# l298driver.net
KiCad netlist of a schematic drawn in EAGLE
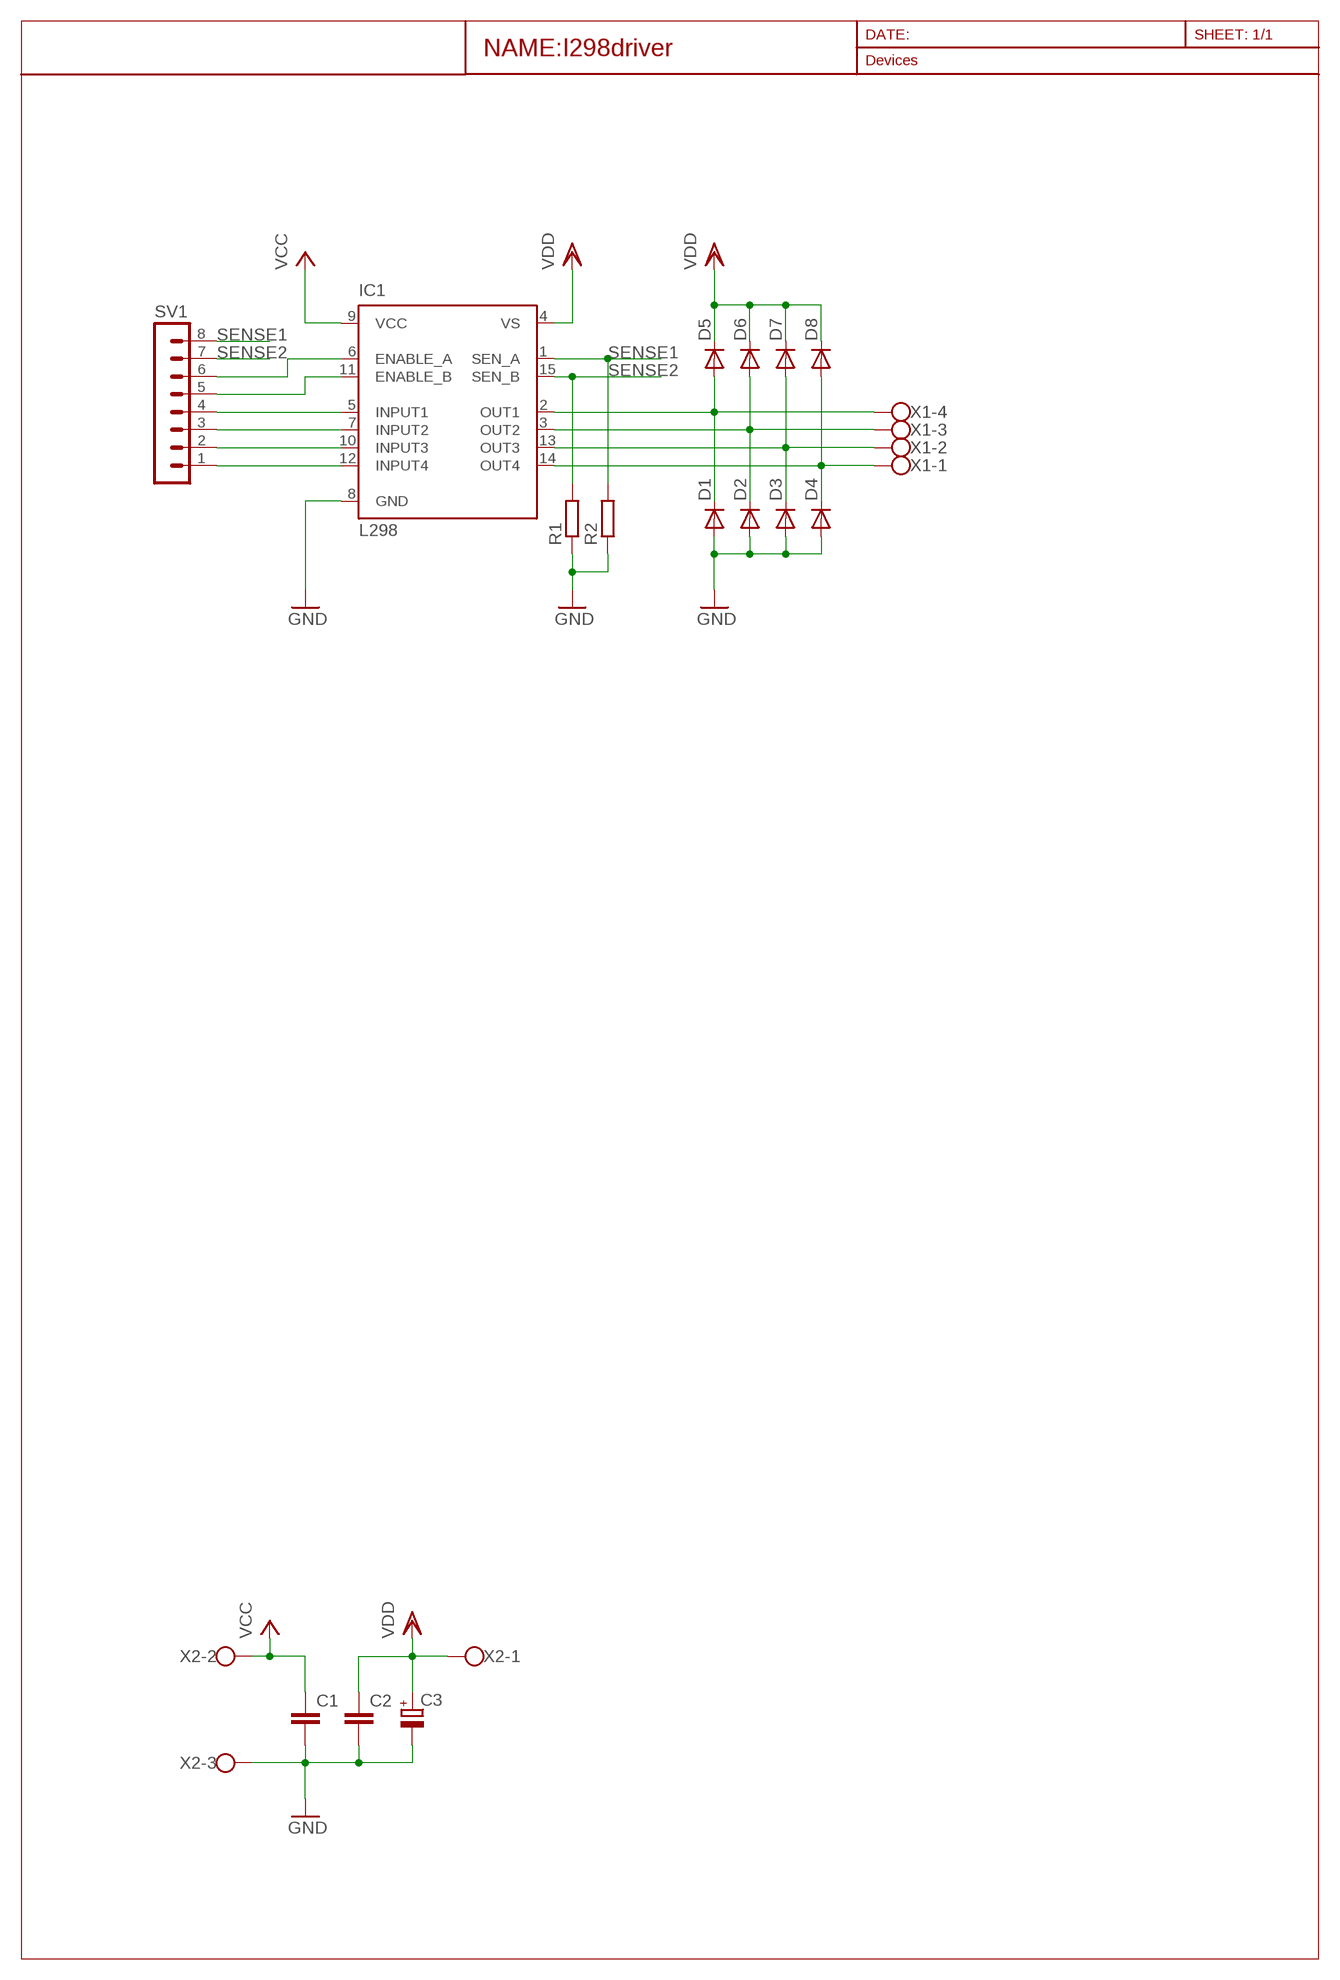
[diagram p0: schematic, sheet 1]

(export (version "E")
  (design (tool "Eeschema 10.0.6"))
  (components
    (comp (ref "C1")
      (value "C-EU050-024X044")
      (footprint "eagle-import:C050-024X044")
      (libsource (lib "eagle-import") (part "C-EU050-024X044"))
    )
    (comp (ref "C2")
      (value "C-EU050-024X044")
      (footprint "eagle-import:C050-024X044")
      (libsource (lib "eagle-import") (part "C-EU050-024X044"))
    )
    (comp (ref "C3")
      (value "CPOL-EUE3.5-10")
      (footprint "eagle-import:E3,5-10")
      (libsource (lib "eagle-import") (part "CPOL-EUE3.5-10"))
    )
    (comp (ref "D1")
      (value "BA157")
      (footprint "eagle-import:P1-10")
      (libsource (lib "eagle-import") (part "BA157"))
    )
    (comp (ref "D2")
      (value "BA157")
      (footprint "eagle-import:P1-10")
      (libsource (lib "eagle-import") (part "BA157"))
    )
    (comp (ref "D3")
      (value "BA157")
      (footprint "eagle-import:P1-10")
      (libsource (lib "eagle-import") (part "BA157"))
    )
    (comp (ref "D4")
      (value "BA157")
      (footprint "eagle-import:P1-10")
      (libsource (lib "eagle-import") (part "BA157"))
    )
    (comp (ref "D5")
      (value "BA157")
      (footprint "eagle-import:P1-10")
      (libsource (lib "eagle-import") (part "BA157"))
    )
    (comp (ref "D6")
      (value "BA157")
      (footprint "eagle-import:P1-10")
      (libsource (lib "eagle-import") (part "BA157"))
    )
    (comp (ref "D7")
      (value "BA157")
      (footprint "eagle-import:P1-10")
      (libsource (lib "eagle-import") (part "BA157"))
    )
    (comp (ref "D8")
      (value "BA157")
      (footprint "eagle-import:P1-10")
      (libsource (lib "eagle-import") (part "BA157"))
    )
    (comp (ref "IC1")
      (value "L298")
      (footprint "eagle-import:MULTIWATT-15")
      (fields (field (name "MPN") "L298N"))
      (libsource (lib "eagle-import") (part "L298"))
    )
    (comp (ref "R1")
      (value "R-EU_RDH/15")
      (footprint "eagle-import:RDH_15")
      (libsource (lib "eagle-import") (part "R-EU_RDH/15"))
    )
    (comp (ref "R2")
      (value "R-EU_RDH/15")
      (footprint "eagle-import:RDH_15")
      (libsource (lib "eagle-import") (part "R-EU_RDH/15"))
    )
    (comp (ref "SV1")
      (value "MA08-1")
      (footprint "eagle-import:MA08-1")
      (libsource (lib "eagle-import") (part "MA08-1"))
    )
    (comp (ref "X1")
      (value "W237-4")
      (footprint "eagle-import:W237-4")
      (libsource (lib "eagle-import") (part "W237-4"))
    )
    (comp (ref "X2")
      (value "W237-103")
      (footprint "eagle-import:W237-103")
      (fields (field (name "MPN") "237-103"))
      (libsource (lib "eagle-import") (part "W237-103"))
    )
  )
  (nets
    (net (code "1") (name "/SENSE1") (class "Default")
      (node (ref "IC1") (pin "1") (pinfunction "SEN_A_1") (pintype "input"))
      (node (ref "R2") (pin "2") (pinfunction "2_2") (pintype "passive"))
      (node (ref "SV1") (pin "8") (pinfunction "8_8") (pintype "passive"))
    )
    (net (code "2") (name "/SENSE2") (class "Default")
      (node (ref "IC1") (pin "15") (pinfunction "SEN_B_15") (pintype "input"))
      (node (ref "R1") (pin "2") (pinfunction "2_2") (pintype "passive"))
      (node (ref "SV1") (pin "7") (pinfunction "7_7") (pintype "passive"))
    )
    (net (code "3") (name "GND") (class "Default")
      (node (ref "C1") (pin "2") (pinfunction "2_2") (pintype "passive"))
      (node (ref "C2") (pin "2") (pinfunction "2_2") (pintype "passive"))
      (node (ref "C3") (pin "-") (pinfunction "-_-") (pintype "passive"))
      (node (ref "D1") (pin "A") (pinfunction "A_A") (pintype "passive"))
      (node (ref "D2") (pin "A") (pinfunction "A_A") (pintype "passive"))
      (node (ref "D3") (pin "A") (pinfunction "A_A") (pintype "passive"))
      (node (ref "D4") (pin "A") (pinfunction "A_A") (pintype "passive"))
      (node (ref "IC1") (pin "8") (pinfunction "GND_8") (pintype "power_in"))
      (node (ref "R1") (pin "1") (pinfunction "1_1") (pintype "passive"))
      (node (ref "R2") (pin "1") (pinfunction "1_1") (pintype "passive"))
      (node (ref "X2") (pin "3") (pinfunction "KL_3") (pintype "passive"))
    )
    (net (code "4") (name "Net-(IC1-ENABLE_A)") (class "Default")
      (node (ref "IC1") (pin "6") (pinfunction "ENABLE_A_6") (pintype "input"))
      (node (ref "SV1") (pin "6") (pinfunction "6_6") (pintype "passive"))
    )
    (net (code "5") (name "Net-(IC1-ENABLE_B)") (class "Default")
      (node (ref "IC1") (pin "11") (pinfunction "ENABLE_B_11") (pintype "input"))
      (node (ref "SV1") (pin "5") (pinfunction "5_5") (pintype "passive"))
    )
    (net (code "6") (name "Net-(IC1-INPUT1)") (class "Default")
      (node (ref "IC1") (pin "5") (pinfunction "INPUT1_5") (pintype "input"))
      (node (ref "SV1") (pin "4") (pinfunction "4_4") (pintype "passive"))
    )
    (net (code "7") (name "Net-(IC1-INPUT2)") (class "Default")
      (node (ref "IC1") (pin "7") (pinfunction "INPUT2_7") (pintype "input"))
      (node (ref "SV1") (pin "3") (pinfunction "3_3") (pintype "passive"))
    )
    (net (code "8") (name "Net-(IC1-INPUT3)") (class "Default")
      (node (ref "IC1") (pin "10") (pinfunction "INPUT3_10") (pintype "input"))
      (node (ref "SV1") (pin "2") (pinfunction "2_2") (pintype "passive"))
    )
    (net (code "9") (name "Net-(IC1-INPUT4)") (class "Default")
      (node (ref "IC1") (pin "12") (pinfunction "INPUT4_12") (pintype "input"))
      (node (ref "SV1") (pin "1") (pinfunction "1_1") (pintype "passive"))
    )
    (net (code "10") (name "Net-(IC1-OUT1)") (class "Default")
      (node (ref "D1") (pin "C") (pinfunction "C_C") (pintype "passive"))
      (node (ref "D5") (pin "A") (pinfunction "A_A") (pintype "passive"))
      (node (ref "IC1") (pin "2") (pinfunction "OUT1_2") (pintype "output"))
      (node (ref "X1") (pin "4") (pinfunction "KL_4") (pintype "passive"))
    )
    (net (code "11") (name "Net-(IC1-OUT2)") (class "Default")
      (node (ref "D2") (pin "C") (pinfunction "C_C") (pintype "passive"))
      (node (ref "D6") (pin "A") (pinfunction "A_A") (pintype "passive"))
      (node (ref "IC1") (pin "3") (pinfunction "OUT2_3") (pintype "output"))
      (node (ref "X1") (pin "3") (pinfunction "KL_3") (pintype "passive"))
    )
    (net (code "12") (name "Net-(IC1-OUT3)") (class "Default")
      (node (ref "D3") (pin "C") (pinfunction "C_C") (pintype "passive"))
      (node (ref "D7") (pin "A") (pinfunction "A_A") (pintype "passive"))
      (node (ref "IC1") (pin "13") (pinfunction "OUT3_13") (pintype "output"))
      (node (ref "X1") (pin "2") (pinfunction "KL_2") (pintype "passive"))
    )
    (net (code "13") (name "Net-(IC1-OUT4)") (class "Default")
      (node (ref "D4") (pin "C") (pinfunction "C_C") (pintype "passive"))
      (node (ref "D8") (pin "A") (pinfunction "A_A") (pintype "passive"))
      (node (ref "IC1") (pin "14") (pinfunction "OUT4_14") (pintype "output"))
      (node (ref "X1") (pin "1") (pinfunction "KL_1") (pintype "passive"))
    )
    (net (code "14") (name "VCC") (class "Default")
      (node (ref "C1") (pin "1") (pinfunction "1_1") (pintype "passive"))
      (node (ref "IC1") (pin "9") (pinfunction "VCC_9") (pintype "power_in"))
      (node (ref "X2") (pin "2") (pinfunction "KL_2") (pintype "passive"))
    )
    (net (code "15") (name "VDD") (class "Default")
      (node (ref "C2") (pin "1") (pinfunction "1_1") (pintype "passive"))
      (node (ref "C3") (pin "+") (pinfunction "+_+") (pintype "passive"))
      (node (ref "D5") (pin "C") (pinfunction "C_C") (pintype "passive"))
      (node (ref "D6") (pin "C") (pinfunction "C_C") (pintype "passive"))
      (node (ref "D7") (pin "C") (pinfunction "C_C") (pintype "passive"))
      (node (ref "D8") (pin "C") (pinfunction "C_C") (pintype "passive"))
      (node (ref "IC1") (pin "4") (pinfunction "VS_4") (pintype "power_in"))
      (node (ref "X2") (pin "1") (pinfunction "KL_1") (pintype "passive"))
    )
  )
)
